# TorqueDroid.net
KiCad netlist of a schematic drawn in EAGLE
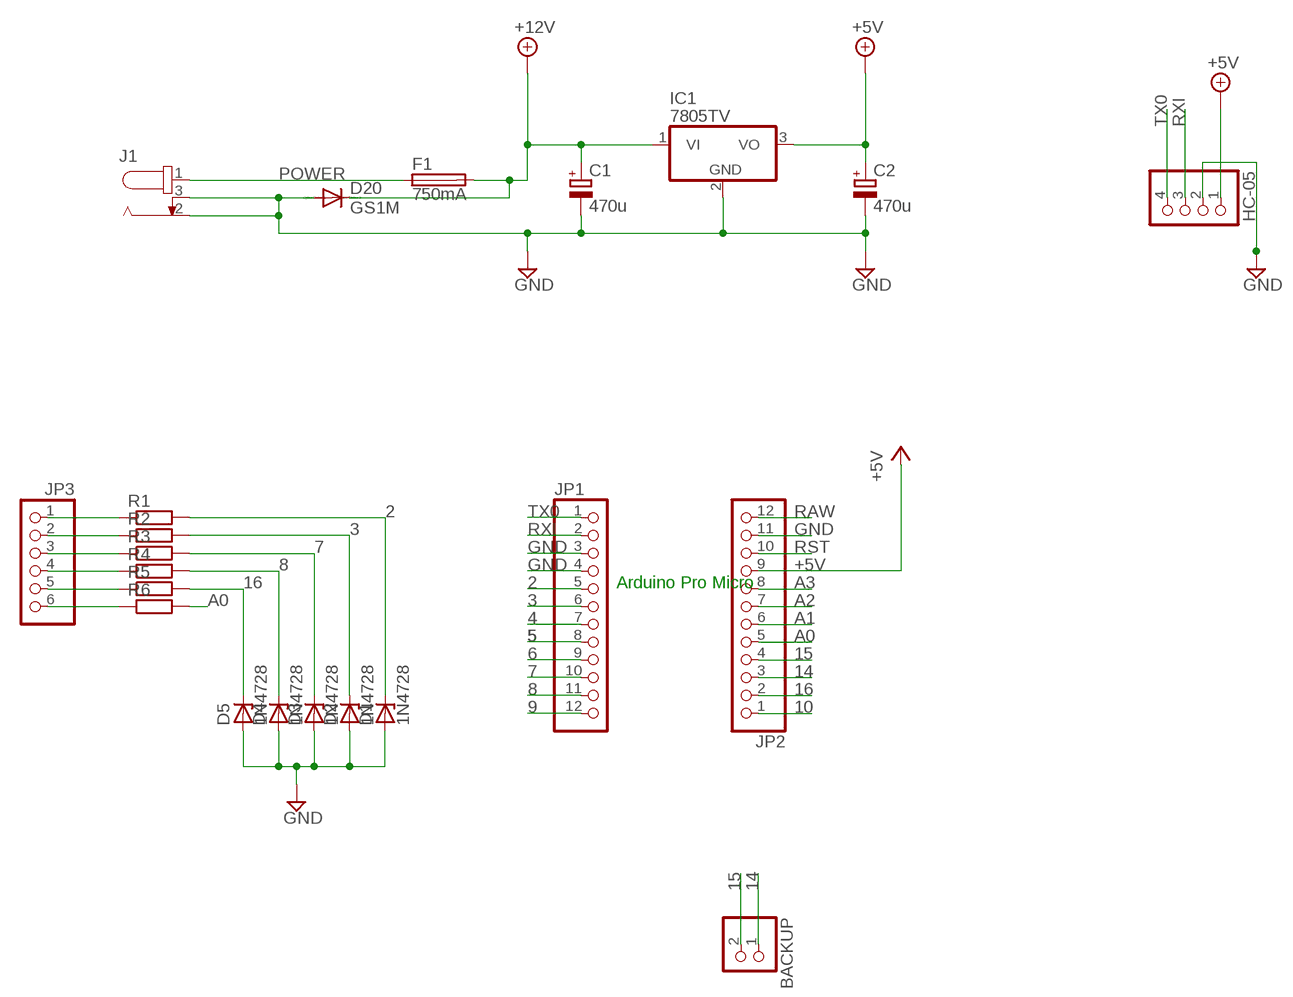
[diagram p0: schematic, sheet 1]

(export (version "E")
  (design (tool "Eeschema 10.0.6"))
  (components
    (comp (ref "BACKUP")
      (value "PINHD-1X2")
      (footprint "eagle-import:1X02")
      (libsource (lib "eagle-import") (part "PINHD-1X2"))
    )
    (comp (ref "C1")
      (value "470u")
      (footprint "eagle-import:E3,5-10")
      (libsource (lib "eagle-import") (part "CPOL-EUE3.5-10"))
    )
    (comp (ref "C2")
      (value "470u")
      (footprint "eagle-import:E3,5-10")
      (libsource (lib "eagle-import") (part "CPOL-EUE3.5-10"))
    )
    (comp (ref "D1")
      (value "1N4728")
      (footprint "eagle-import:DO41Z10")
      (libsource (lib "eagle-import") (part "1N4728"))
    )
    (comp (ref "D2")
      (value "1N4728")
      (footprint "eagle-import:DO41Z10")
      (libsource (lib "eagle-import") (part "1N4728"))
    )
    (comp (ref "D3")
      (value "1N4728")
      (footprint "eagle-import:DO41Z10")
      (libsource (lib "eagle-import") (part "1N4728"))
    )
    (comp (ref "D4")
      (value "1N4728")
      (footprint "eagle-import:DO41Z10")
      (libsource (lib "eagle-import") (part "1N4728"))
    )
    (comp (ref "D5")
      (value "1N4728")
      (footprint "eagle-import:DO41Z10")
      (libsource (lib "eagle-import") (part "1N4728"))
    )
    (comp (ref "D20")
      (value "GS1M")
      (footprint "eagle-import:SMA")
      (libsource (lib "eagle-import") (part "S1M"))
    )
    (comp (ref "F1")
      (value "750mA")
      (footprint "eagle-import:MF-SMDF050")
      (libsource (lib "eagle-import") (part "MF-SMDF150"))
    )
    (comp (ref "HC-05")
      (value "PINHD-1X4")
      (footprint "eagle-import:1X04")
      (libsource (lib "eagle-import") (part "PINHD-1X4"))
    )
    (comp (ref "IC1")
      (value "7805TV")
      (footprint "eagle-import:TO220V")
      (libsource (lib "eagle-import") (part "78TV05"))
    )
    (comp (ref "J1")
      (value "694102303002")
      (footprint "eagle-import:69410X303002")
      (libsource (lib "eagle-import") (part "694102303002"))
    )
    (comp (ref "JP1")
      (value "PINHD-1X12")
      (footprint "eagle-import:1X12")
      (libsource (lib "eagle-import") (part "PINHD-1X12"))
    )
    (comp (ref "JP2")
      (value "PINHD-1X12")
      (footprint "eagle-import:1X12")
      (libsource (lib "eagle-import") (part "PINHD-1X12"))
    )
    (comp (ref "JP3")
      (value "PINHD-1X6/90")
      (footprint "eagle-import:1X06_90")
      (libsource (lib "eagle-import") (part "PINHD-1X6/90"))
    )
    (comp (ref "R1")
      (value "R-EU_R0805")
      (footprint "eagle-import:R0805")
      (libsource (lib "eagle-import") (part "R-EU_R0805"))
    )
    (comp (ref "R2")
      (value "R-EU_R0805")
      (footprint "eagle-import:R0805")
      (libsource (lib "eagle-import") (part "R-EU_R0805"))
    )
    (comp (ref "R3")
      (value "R-EU_R0805")
      (footprint "eagle-import:R0805")
      (libsource (lib "eagle-import") (part "R-EU_R0805"))
    )
    (comp (ref "R4")
      (value "R-EU_R0805")
      (footprint "eagle-import:R0805")
      (libsource (lib "eagle-import") (part "R-EU_R0805"))
    )
    (comp (ref "R5")
      (value "R-EU_R0805")
      (footprint "eagle-import:R0805")
      (libsource (lib "eagle-import") (part "R-EU_R0805"))
    )
    (comp (ref "R6")
      (value "R-EU_R0805")
      (footprint "eagle-import:R0805")
      (libsource (lib "eagle-import") (part "R-EU_R0805"))
    )
  )
  (nets
    (net (code "1") (name "+5V") (class "Default")
      (node (ref "C2") (pin "+") (pinfunction "+_+") (pintype "passive"))
      (node (ref "HC-05") (pin "1") (pinfunction "1_1") (pintype "passive"))
      (node (ref "IC1") (pin "3") (pinfunction "VO_3") (pintype "passive"))
      (node (ref "JP2") (pin "9") (pinfunction "9_9") (pintype "passive"))
    )
    (net (code "2") (name "+12V") (class "Default")
      (node (ref "C1") (pin "+") (pinfunction "+_+") (pintype "passive"))
      (node (ref "D20") (pin "C") (pinfunction "C_C") (pintype "passive"))
      (node (ref "F1") (pin "2") (pinfunction "2_2") (pintype "passive"))
      (node (ref "IC1") (pin "1") (pinfunction "VI_1") (pintype "input"))
    )
    (net (code "3") (name "/2") (class "Default")
      (node (ref "D1") (pin "C") (pinfunction "C_C") (pintype "passive"))
      (node (ref "JP1") (pin "5") (pinfunction "5_5") (pintype "passive"))
      (node (ref "R1") (pin "2") (pinfunction "2_2") (pintype "passive"))
    )
    (net (code "4") (name "/3") (class "Default")
      (node (ref "D2") (pin "C") (pinfunction "C_C") (pintype "passive"))
      (node (ref "JP1") (pin "6") (pinfunction "6_6") (pintype "passive"))
      (node (ref "R2") (pin "2") (pinfunction "2_2") (pintype "passive"))
    )
    (net (code "5") (name "/4") (class "Default")
      (node (ref "JP1") (pin "7") (pinfunction "7_7") (pintype "passive"))
    )
    (net (code "6") (name "/5") (class "Default")
      (node (ref "JP1") (pin "8") (pinfunction "8_8") (pintype "passive"))
    )
    (net (code "7") (name "/6") (class "Default")
      (node (ref "JP1") (pin "9") (pinfunction "9_9") (pintype "passive"))
    )
    (net (code "8") (name "/7") (class "Default")
      (node (ref "D3") (pin "C") (pinfunction "C_C") (pintype "passive"))
      (node (ref "JP1") (pin "10") (pinfunction "10_10") (pintype "passive"))
      (node (ref "R3") (pin "2") (pinfunction "2_2") (pintype "passive"))
    )
    (net (code "9") (name "/8") (class "Default")
      (node (ref "D4") (pin "C") (pinfunction "C_C") (pintype "passive"))
      (node (ref "JP1") (pin "11") (pinfunction "11_11") (pintype "passive"))
      (node (ref "R4") (pin "2") (pinfunction "2_2") (pintype "passive"))
    )
    (net (code "10") (name "/9") (class "Default")
      (node (ref "JP1") (pin "12") (pinfunction "12_12") (pintype "passive"))
    )
    (net (code "11") (name "/10") (class "Default")
      (node (ref "JP2") (pin "1") (pinfunction "1_1") (pintype "passive"))
    )
    (net (code "12") (name "/14") (class "Default")
      (node (ref "BACKUP") (pin "1") (pinfunction "1_1") (pintype "passive"))
      (node (ref "JP2") (pin "3") (pinfunction "3_3") (pintype "passive"))
    )
    (net (code "13") (name "/15") (class "Default")
      (node (ref "BACKUP") (pin "2") (pinfunction "2_2") (pintype "passive"))
      (node (ref "JP2") (pin "4") (pinfunction "4_4") (pintype "passive"))
    )
    (net (code "14") (name "/16") (class "Default")
      (node (ref "D5") (pin "C") (pinfunction "C_C") (pintype "passive"))
      (node (ref "JP2") (pin "2") (pinfunction "2_2") (pintype "passive"))
      (node (ref "R5") (pin "2") (pinfunction "2_2") (pintype "passive"))
    )
    (net (code "15") (name "/A0") (class "Default")
      (node (ref "JP2") (pin "5") (pinfunction "5_5") (pintype "passive"))
      (node (ref "R6") (pin "2") (pinfunction "2_2") (pintype "passive"))
    )
    (net (code "16") (name "/A1") (class "Default")
      (node (ref "JP2") (pin "6") (pinfunction "6_6") (pintype "passive"))
    )
    (net (code "17") (name "/A2") (class "Default")
      (node (ref "JP2") (pin "7") (pinfunction "7_7") (pintype "passive"))
    )
    (net (code "18") (name "/A3") (class "Default")
      (node (ref "JP2") (pin "8") (pinfunction "8_8") (pintype "passive"))
    )
    (net (code "19") (name "/POWER") (class "Default")
      (node (ref "F1") (pin "1") (pinfunction "1_1") (pintype "passive"))
      (node (ref "J1") (pin "1") (pinfunction "1_1") (pintype "passive"))
    )
    (net (code "20") (name "/RAW") (class "Default")
      (node (ref "JP2") (pin "12") (pinfunction "12_12") (pintype "passive"))
    )
    (net (code "21") (name "/RST") (class "Default")
      (node (ref "JP2") (pin "10") (pinfunction "10_10") (pintype "passive"))
    )
    (net (code "22") (name "/RXI") (class "Default")
      (node (ref "HC-05") (pin "3") (pinfunction "3_3") (pintype "passive"))
      (node (ref "JP1") (pin "2") (pinfunction "2_2") (pintype "passive"))
    )
    (net (code "23") (name "/TX0") (class "Default")
      (node (ref "HC-05") (pin "4") (pinfunction "4_4") (pintype "passive"))
      (node (ref "JP1") (pin "1") (pinfunction "1_1") (pintype "passive"))
    )
    (net (code "24") (name "GND") (class "Default")
      (node (ref "C1") (pin "-") (pinfunction "-_-") (pintype "passive"))
      (node (ref "C2") (pin "-") (pinfunction "-_-") (pintype "passive"))
      (node (ref "D1") (pin "A") (pinfunction "A_A") (pintype "passive"))
      (node (ref "D2") (pin "A") (pinfunction "A_A") (pintype "passive"))
      (node (ref "D20") (pin "A") (pinfunction "A_A") (pintype "passive"))
      (node (ref "D3") (pin "A") (pinfunction "A_A") (pintype "passive"))
      (node (ref "D4") (pin "A") (pinfunction "A_A") (pintype "passive"))
      (node (ref "D5") (pin "A") (pinfunction "A_A") (pintype "passive"))
      (node (ref "HC-05") (pin "2") (pinfunction "2_2") (pintype "passive"))
      (node (ref "IC1") (pin "2") (pinfunction "GND_2") (pintype "passive"))
      (node (ref "J1") (pin "2") (pinfunction "2_2") (pintype "passive"))
      (node (ref "J1") (pin "3") (pinfunction "3_3") (pintype "passive"))
      (node (ref "JP1") (pin "3") (pinfunction "3_3") (pintype "passive"))
      (node (ref "JP1") (pin "4") (pinfunction "4_4") (pintype "passive"))
      (node (ref "JP2") (pin "11") (pinfunction "11_11") (pintype "passive"))
    )
    (net (code "25") (name "Net-(JP3-Pad1)") (class "Default")
      (node (ref "JP3") (pin "1") (pinfunction "1_1") (pintype "passive"))
      (node (ref "R1") (pin "1") (pinfunction "1_1") (pintype "passive"))
    )
    (net (code "26") (name "Net-(JP3-Pad2)") (class "Default")
      (node (ref "JP3") (pin "2") (pinfunction "2_2") (pintype "passive"))
      (node (ref "R2") (pin "1") (pinfunction "1_1") (pintype "passive"))
    )
    (net (code "27") (name "Net-(JP3-Pad3)") (class "Default")
      (node (ref "JP3") (pin "3") (pinfunction "3_3") (pintype "passive"))
      (node (ref "R3") (pin "1") (pinfunction "1_1") (pintype "passive"))
    )
    (net (code "28") (name "Net-(JP3-Pad4)") (class "Default")
      (node (ref "JP3") (pin "4") (pinfunction "4_4") (pintype "passive"))
      (node (ref "R4") (pin "1") (pinfunction "1_1") (pintype "passive"))
    )
    (net (code "29") (name "Net-(JP3-Pad5)") (class "Default")
      (node (ref "JP3") (pin "5") (pinfunction "5_5") (pintype "passive"))
      (node (ref "R5") (pin "1") (pinfunction "1_1") (pintype "passive"))
    )
    (net (code "30") (name "Net-(JP3-Pad6)") (class "Default")
      (node (ref "JP3") (pin "6") (pinfunction "6_6") (pintype "passive"))
      (node (ref "R6") (pin "1") (pinfunction "1_1") (pintype "passive"))
    )
  )
)
